# 01_MCU.net
KiCad netlist of a schematic drawn in Altium Designer
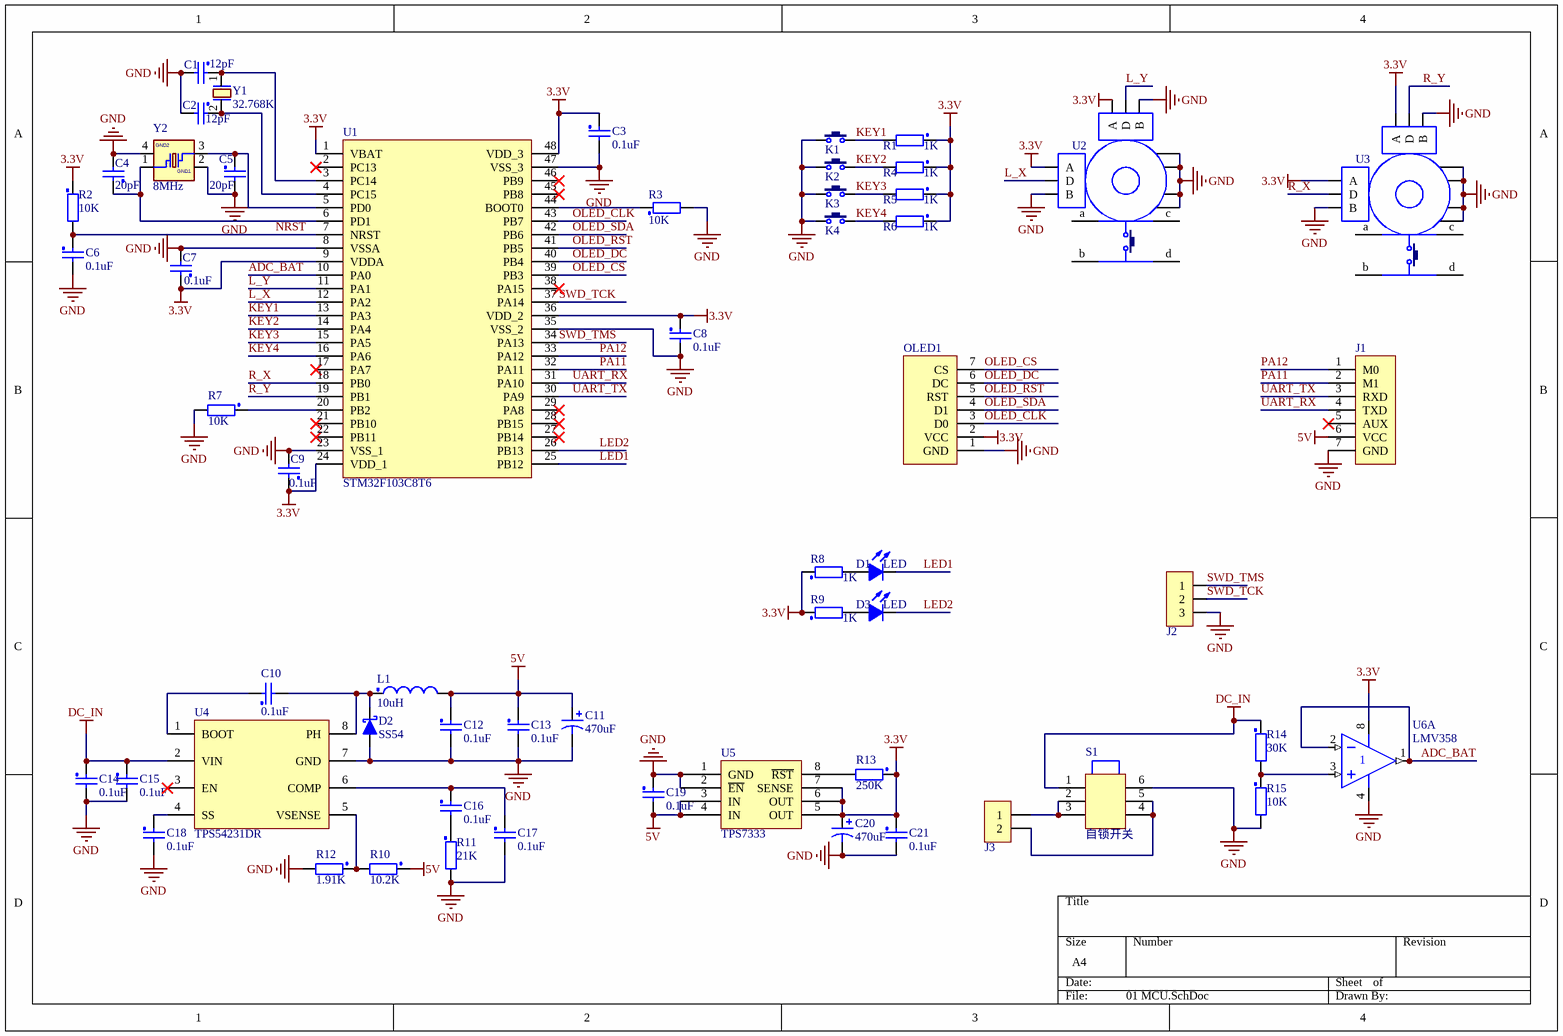
[diagram p0: 01 MCU.SchDoc]

(export (version "E")
  (design (tool "Eeschema 10.0.6"))
  (components
    (comp (ref "C1")
      (value "12pF")
      (footprint "cap0603")
      (description "贴片电容")
      (fields (field (name "PUBLISHER") "Altium Limited"))
      (libsource (lib "元件库") (part "Cap"))
    )
    (comp (ref "C2")
      (value "12pF")
      (footprint "cap0603")
      (description "贴片电容")
      (fields (field (name "PUBLISHER") "Altium Limited"))
      (libsource (lib "元件库") (part "Cap"))
    )
    (comp (ref "C3")
      (value "0.1uF")
      (footprint "cap0603")
      (description "贴片电容")
      (fields (field (name "PUBLISHER") "Altium Limited"))
      (libsource (lib "元件库") (part "Cap"))
    )
    (comp (ref "C4")
      (value "20pF")
      (footprint "cap0603")
      (description "贴片电容")
      (fields (field (name "PUBLISHER") "Altium Limited"))
      (libsource (lib "元件库") (part "Cap"))
    )
    (comp (ref "C5")
      (value "20pF")
      (footprint "cap0603")
      (description "贴片电容")
      (fields (field (name "PUBLISHER") "Altium Limited"))
      (libsource (lib "元件库") (part "Cap"))
    )
    (comp (ref "C6")
      (value "0.1uF")
      (footprint "cap0603")
      (description "贴片电容")
      (fields (field (name "PUBLISHER") "Altium Limited"))
      (libsource (lib "元件库") (part "Cap"))
    )
    (comp (ref "C7")
      (value "0.1uF")
      (footprint "cap0603")
      (description "贴片电容")
      (fields (field (name "PUBLISHER") "Altium Limited"))
      (libsource (lib "元件库") (part "Cap"))
    )
    (comp (ref "C8")
      (value "0.1uF")
      (footprint "cap0603")
      (description "贴片电容")
      (fields (field (name "PUBLISHER") "Altium Limited"))
      (libsource (lib "元件库") (part "Cap"))
    )
    (comp (ref "C9")
      (value "0.1uF")
      (footprint "cap0603")
      (description "贴片电容")
      (fields (field (name "PUBLISHER") "Altium Limited"))
      (libsource (lib "元件库") (part "Cap"))
    )
    (comp (ref "C10")
      (value "0.1uF")
      (footprint "cap0603")
      (description "贴片电容")
      (fields (field (name "PUBLISHER") "Altium Limited"))
      (libsource (lib "元件库") (part "Cap"))
    )
    (comp (ref "C11")
      (value "470uF")
      (footprint "Cap8x10.5mm")
      (description "贴片电解电容 8*10.5mm")
      (fields (field (name "PUBLISHER") "Altium Limited"))
      (libsource (lib "元件库") (part "Cap Pol"))
    )
    (comp (ref "C12")
      (value "0.1uF")
      (footprint "cap0603")
      (description "贴片电容")
      (fields (field (name "PUBLISHER") "Altium Limited"))
      (libsource (lib "元件库") (part "Cap"))
    )
    (comp (ref "C13")
      (value "0.1uF")
      (footprint "cap0603")
      (description "贴片电容")
      (fields (field (name "PUBLISHER") "Altium Limited"))
      (libsource (lib "元件库") (part "Cap"))
    )
    (comp (ref "C14")
      (value "0.1uF")
      (footprint "cap0603")
      (description "贴片电容")
      (fields (field (name "PUBLISHER") "Altium Limited"))
      (libsource (lib "元件库") (part "Cap"))
    )
    (comp (ref "C15")
      (value "0.1uF")
      (footprint "cap0603")
      (description "贴片电容")
      (fields (field (name "PUBLISHER") "Altium Limited"))
      (libsource (lib "元件库") (part "Cap"))
    )
    (comp (ref "C16")
      (value "0.1uF")
      (footprint "cap0603")
      (description "贴片电容")
      (fields (field (name "PUBLISHER") "Altium Limited"))
      (libsource (lib "元件库") (part "Cap"))
    )
    (comp (ref "C17")
      (value "0.1uF")
      (footprint "cap0603")
      (description "贴片电容")
      (fields (field (name "PUBLISHER") "Altium Limited"))
      (libsource (lib "元件库") (part "Cap"))
    )
    (comp (ref "C18")
      (value "0.1uF")
      (footprint "cap0603")
      (description "贴片电容")
      (fields (field (name "PUBLISHER") "Altium Limited"))
      (libsource (lib "元件库") (part "Cap"))
    )
    (comp (ref "C19")
      (value "0.1uF")
      (footprint "cap0603")
      (description "贴片电容")
      (fields (field (name "PUBLISHER") "Altium Limited"))
      (libsource (lib "元件库") (part "Cap"))
    )
    (comp (ref "C20")
      (value "470uF")
      (footprint "Cap8x10.5mm")
      (description "贴片电解电容 8*10.5mm")
      (fields (field (name "PUBLISHER") "Altium Limited"))
      (libsource (lib "元件库") (part "Cap Pol"))
    )
    (comp (ref "C21")
      (value "0.1uF")
      (footprint "cap0603")
      (description "贴片电容")
      (fields (field (name "PUBLISHER") "Altium Limited"))
      (libsource (lib "元件库") (part "Cap"))
    )
    (comp (ref "D1")
      (value "LED")
      (footprint "LED")
      (description "贴片0805")
      (fields (field (name "PUBLISHER") "Altium Limited"))
      (libsource (lib "元件库") (part "LED"))
    )
    (comp (ref "D2")
      (value "SS54")
      (footprint "SMA(DO-214AC)")
      (description "Schottky Diode")
      (fields (field (name "PUBLISHER") "Altium Limited"))
      (libsource (lib "元件库") (part "D Schottky"))
    )
    (comp (ref "D3")
      (value "LED")
      (footprint "LED")
      (description "贴片0805")
      (fields (field (name "PUBLISHER") "Altium Limited"))
      (libsource (lib "元件库") (part "LED"))
    )
    (comp (ref "J1")
      (value "1x7m")
      (footprint "uart_nrf24l01")
      (description "2.54mm母排座")
      (libsource (lib "元件库") (part "无线串口模块"))
    )
    (comp (ref "J2")
      (value "1X3")
      (footprint "HDR-1X3_SWD")
      (description "2.54mm公排针")
      (fields (field (name "版权归属") "源创客"))
      (libsource (lib "元件库") (part "Header 3"))
    )
    (comp (ref "J3")
      (value "1X2")
      (footprint "HDR-1X2")
      (description "不用焊")
      (fields (field (name "版权归属") "源创客"))
      (libsource (lib "元件库") (part "Header 2"))
    )
    (comp (ref "K1")
      (value "KEY")
      (footprint "key")
      (description "按键")
      (fields (field (name "版权归属") "源创客"))
      (libsource (lib "元件库") (part "KEY"))
    )
    (comp (ref "K2")
      (value "KEY")
      (footprint "key")
      (description "按键")
      (fields (field (name "版权归属") "源创客"))
      (libsource (lib "元件库") (part "KEY"))
    )
    (comp (ref "K3")
      (value "KEY")
      (footprint "key")
      (description "按键")
      (fields (field (name "版权归属") "源创客"))
      (libsource (lib "元件库") (part "KEY"))
    )
    (comp (ref "K4")
      (value "KEY")
      (footprint "key")
      (description "按键")
      (fields (field (name "版权归属") "源创客"))
      (libsource (lib "元件库") (part "KEY"))
    )
    (comp (ref "L1")
      (value "10uH")
      (footprint "CD43")
      (description "贴片功率电感")
      (fields (field (name "PUBLISHER") "Altium Limited"))
      (libsource (lib "元件库") (part "Inductor"))
    )
    (comp (ref "OLED1")
      (value "2.541x7母排")
      (footprint "LQ_OLED128X64去丝印")
      (libsource (lib "四轮组原理图元件库") (part "OLED"))
    )
    (comp (ref "R1")
      (value "1K")
      (footprint "res0603")
      (description "贴片电阻")
      (fields (field (name "PUBLISHER") "Altium Limited"))
      (libsource (lib "") (part "Res_1"))
    )
    (comp (ref "R2")
      (value "10K")
      (footprint "res0603")
      (description "贴片电阻")
      (fields (field (name "PUBLISHER") "Altium Limited"))
      (libsource (lib "元件库") (part "Res"))
    )
    (comp (ref "R3")
      (value "10K")
      (footprint "res0603")
      (description "贴片电阻")
      (fields (field (name "PUBLISHER") "Altium Limited"))
      (libsource (lib "") (part "Res_2"))
    )
    (comp (ref "R4")
      (value "1K")
      (footprint "res0603")
      (description "贴片电阻")
      (fields (field (name "PUBLISHER") "Altium Limited"))
      (libsource (lib "") (part "Res_1"))
    )
    (comp (ref "R5")
      (value "1K")
      (footprint "res0603")
      (description "贴片电阻")
      (fields (field (name "PUBLISHER") "Altium Limited"))
      (libsource (lib "") (part "Res_1"))
    )
    (comp (ref "R6")
      (value "1K")
      (footprint "res0603")
      (description "贴片电阻")
      (fields (field (name "PUBLISHER") "Altium Limited"))
      (libsource (lib "") (part "Res_1"))
    )
    (comp (ref "R7")
      (value "10K")
      (footprint "res0603")
      (description "贴片电阻")
      (fields (field (name "PUBLISHER") "Altium Limited"))
      (libsource (lib "") (part "Res_1"))
    )
    (comp (ref "R8")
      (value "1K")
      (footprint "res0603")
      (description "贴片电阻")
      (fields (field (name "PUBLISHER") "Altium Limited"))
      (libsource (lib "") (part "Res_2"))
    )
    (comp (ref "R9")
      (value "1K")
      (footprint "res0603")
      (description "贴片电阻")
      (fields (field (name "PUBLISHER") "Altium Limited"))
      (libsource (lib "") (part "Res_2"))
    )
    (comp (ref "R10")
      (value "10.2K")
      (footprint "res0603")
      (description "贴片电阻")
      (fields (field (name "PUBLISHER") "Altium Limited"))
      (libsource (lib "") (part "Res_1"))
    )
    (comp (ref "R11")
      (value "21K")
      (footprint "res0603")
      (description "贴片电阻")
      (fields (field (name "PUBLISHER") "Altium Limited"))
      (libsource (lib "元件库") (part "Res"))
    )
    (comp (ref "R12")
      (value "1.91K")
      (footprint "res0603")
      (description "贴片电阻")
      (fields (field (name "PUBLISHER") "Altium Limited"))
      (libsource (lib "") (part "Res_1"))
    )
    (comp (ref "R13")
      (value "250K")
      (footprint "res0603")
      (description "贴片电阻")
      (fields (field (name "PUBLISHER") "Altium Limited"))
      (libsource (lib "") (part "Res_1"))
    )
    (comp (ref "R14")
      (value "30K")
      (footprint "res0603")
      (description "贴片电阻")
      (fields (field (name "PUBLISHER") "Altium Limited"))
      (libsource (lib "元件库") (part "Res"))
    )
    (comp (ref "R15")
      (value "10K")
      (footprint "res0603")
      (description "贴片电阻")
      (fields (field (name "PUBLISHER") "Altium Limited"))
      (libsource (lib "元件库") (part "Res"))
    )
    (comp (ref "S1")
      (value "自锁开关")
      (footprint "6pswitch7*7mm")
      (description "按键六脚开关,自锁7*7mm")
      (libsource (lib "元件库") (part "自锁开关"))
    )
    (comp (ref "U1")
      (value "STM32F103C8T6")
      (footprint "LQFP-48_7x7x05P")
      (libsource (lib "元件库") (part "STM32F103C8T6"))
    )
    (comp (ref "U2")
      (value "手柄摇杆电位器")
      (footprint "摇杆")
      (description "型号RKJXV1224005")
      (libsource (lib "元件库") (part "手柄摇杆电位器"))
    )
    (comp (ref "U3")
      (value "手柄摇杆电位器")
      (footprint "摇杆")
      (description "型号RKJXV1224005")
      (libsource (lib "元件库") (part "手柄摇杆电位器"))
    )
    (comp (ref "U4")
      (value "TPS54231DR")
      (footprint "SOIC-8_150mil")
      (description "DC-DC芯片,3.5V~28V输入,2A输出")
      (libsource (lib "元件库") (part "TPS54231DR"))
    )
    (comp (ref "U5")
      (value "TPS7333")
      (footprint "SOP8")
      (description "TPS73系列电源IC")
      (libsource (lib "元件库") (part "TPS7333"))
    )
    (comp (ref "U6")
      (value "LMV358")
      (footprint "OPA2350")
      (description "运放")
      (fields (field (name "PUBLISHER") "Altium Limited"))
      (libsource (lib "元件库") (part "LMV358"))
    )
    (comp (ref "Y1")
      (value "32.768K")
      (footprint "SMD3215")
      (description "晶振 32.768KHZ 12.5PF")
      (libsource (lib "元件库") (part "CRYSTAL"))
    )
    (comp (ref "Y2")
      (value "8MHz")
      (footprint "SMD3225")
      (description "无源晶振 8MHZ 20pF 3.2X2.5MM SMD")
      (libsource (lib "元件库") (part "CRYSTAL_JXS63"))
    )
  )
  (nets
    (net (code "1") (name "/ADC_BAT") (class "Default")
      (node (ref "U1") (pin "10") (pinfunction "PA0_10") (pintype "passive"))
      (node (ref "U6") (pin "1") (pinfunction "OUT_1") (pintype "output"))
      (node (ref "U6") (pin "2") (pinfunction "IN-_2") (pintype "input"))
    )
    (net (code "2") (name "/KEY1") (class "Default")
      (node (ref "K1") (pin "2") (pinfunction "2_2") (pintype "passive"))
      (node (ref "R1") (pin "2") (pinfunction "2_2") (pintype "passive"))
      (node (ref "U1") (pin "13") (pinfunction "PA3_13") (pintype "passive"))
    )
    (net (code "3") (name "/KEY2") (class "Default")
      (node (ref "K2") (pin "2") (pinfunction "2_2") (pintype "passive"))
      (node (ref "R4") (pin "2") (pinfunction "2_2") (pintype "passive"))
      (node (ref "U1") (pin "14") (pinfunction "PA4_14") (pintype "passive"))
    )
    (net (code "4") (name "/KEY3") (class "Default")
      (node (ref "K3") (pin "2") (pinfunction "2_2") (pintype "passive"))
      (node (ref "R5") (pin "2") (pinfunction "2_2") (pintype "passive"))
      (node (ref "U1") (pin "15") (pinfunction "PA5_15") (pintype "passive"))
    )
    (net (code "5") (name "/KEY4") (class "Default")
      (node (ref "K4") (pin "2") (pinfunction "2_2") (pintype "passive"))
      (node (ref "R6") (pin "2") (pinfunction "2_2") (pintype "passive"))
      (node (ref "U1") (pin "16") (pinfunction "PA6_16") (pintype "passive"))
    )
    (net (code "6") (name "/LED1") (class "Default")
      (node (ref "D1") (pin "2") (pinfunction "K_2") (pintype "passive"))
      (node (ref "U1") (pin "25") (pinfunction "PB12_25") (pintype "passive"))
    )
    (net (code "7") (name "/LED2") (class "Default")
      (node (ref "D3") (pin "2") (pinfunction "K_2") (pintype "passive"))
      (node (ref "U1") (pin "26") (pinfunction "PB13_26") (pintype "passive"))
    )
    (net (code "8") (name "/L_X") (class "Default")
      (node (ref "U1") (pin "12") (pinfunction "PA2_12") (pintype "passive"))
      (node (ref "U2") (pin "2") (pinfunction "D_2") (pintype "passive"))
    )
    (net (code "9") (name "/L_Y") (class "Default")
      (node (ref "U1") (pin "11") (pinfunction "PA1_11") (pintype "passive"))
      (node (ref "U2") (pin "5") (pinfunction "D_5") (pintype "passive"))
    )
    (net (code "10") (name "/NRST") (class "Default")
      (node (ref "C6") (pin "1") (pinfunction "1_1") (pintype "passive"))
      (node (ref "R2") (pin "2") (pinfunction "2_2") (pintype "passive"))
      (node (ref "U1") (pin "7") (pinfunction "NRST_7") (pintype "passive"))
    )
    (net (code "11") (name "/OLED_CLK") (class "Default")
      (node (ref "OLED1") (pin "3") (pinfunction "D0_3") (pintype "passive"))
      (node (ref "U1") (pin "43") (pinfunction "PB7_43") (pintype "passive"))
    )
    (net (code "12") (name "/OLED_CS") (class "Default")
      (node (ref "OLED1") (pin "7") (pinfunction "CS_7") (pintype "passive"))
      (node (ref "U1") (pin "39") (pinfunction "PB3_39") (pintype "passive"))
    )
    (net (code "13") (name "/OLED_DC") (class "Default")
      (node (ref "OLED1") (pin "6") (pinfunction "DC_6") (pintype "passive"))
      (node (ref "U1") (pin "40") (pinfunction "PB4_40") (pintype "passive"))
    )
    (net (code "14") (name "/OLED_RST") (class "Default")
      (node (ref "OLED1") (pin "5") (pinfunction "RST_5") (pintype "passive"))
      (node (ref "U1") (pin "41") (pinfunction "PB5_41") (pintype "passive"))
    )
    (net (code "15") (name "/OLED_SDA") (class "Default")
      (node (ref "OLED1") (pin "4") (pinfunction "D1_4") (pintype "passive"))
      (node (ref "U1") (pin "42") (pinfunction "PB6_42") (pintype "passive"))
    )
    (net (code "16") (name "/PA11") (class "Default")
      (node (ref "J1") (pin "2") (pinfunction "M1_2") (pintype "passive"))
      (node (ref "U1") (pin "32") (pinfunction "PA11_32") (pintype "passive"))
    )
    (net (code "17") (name "/PA12") (class "Default")
      (node (ref "J1") (pin "1") (pinfunction "M0_1") (pintype "passive"))
      (node (ref "U1") (pin "33") (pinfunction "PA12_33") (pintype "passive"))
    )
    (net (code "18") (name "/R_X") (class "Default")
      (node (ref "U1") (pin "18") (pinfunction "PB0_18") (pintype "passive"))
      (node (ref "U3") (pin "2") (pinfunction "D_2") (pintype "passive"))
    )
    (net (code "19") (name "/R_Y") (class "Default")
      (node (ref "U1") (pin "19") (pinfunction "PB1_19") (pintype "passive"))
      (node (ref "U3") (pin "5") (pinfunction "D_5") (pintype "passive"))
    )
    (net (code "20") (name "/SWD_TCK") (class "Default")
      (node (ref "J2") (pin "2") (pinfunction "2_2") (pintype "passive"))
      (node (ref "U1") (pin "37") (pinfunction "PA14_37") (pintype "passive"))
    )
    (net (code "21") (name "/SWD_TMS") (class "Default")
      (node (ref "J2") (pin "1") (pinfunction "1_1") (pintype "passive"))
      (node (ref "U1") (pin "34") (pinfunction "PA13_34") (pintype "passive"))
    )
    (net (code "22") (name "/UART_RX") (class "Default")
      (node (ref "J1") (pin "4") (pinfunction "TXD_4") (pintype "passive"))
      (node (ref "U1") (pin "31") (pinfunction "PA10_31") (pintype "passive"))
    )
    (net (code "23") (name "/UART_TX") (class "Default")
      (node (ref "J1") (pin "3") (pinfunction "RXD_3") (pintype "passive"))
      (node (ref "U1") (pin "30") (pinfunction "PA9_30") (pintype "passive"))
    )
    (net (code "24") (name "3.3V") (class "Default")
      (node (ref "C20") (pin "1") (pinfunction "1_1") (pintype "passive"))
      (node (ref "C21") (pin "1") (pinfunction "1_1") (pintype "passive"))
      (node (ref "C3") (pin "1") (pinfunction "1_1") (pintype "passive"))
      (node (ref "C7") (pin "1") (pinfunction "1_1") (pintype "passive"))
      (node (ref "C8") (pin "1") (pinfunction "1_1") (pintype "passive"))
      (node (ref "C9") (pin "1") (pinfunction "1_1") (pintype "passive"))
      (node (ref "OLED1") (pin "2") (pinfunction "VCC_2") (pintype "passive"))
      (node (ref "R1") (pin "1") (pinfunction "1_1") (pintype "passive"))
      (node (ref "R13") (pin "1") (pinfunction "1_1") (pintype "passive"))
      (node (ref "R2") (pin "1") (pinfunction "1_1") (pintype "passive"))
      (node (ref "R4") (pin "1") (pinfunction "1_1") (pintype "passive"))
      (node (ref "R5") (pin "1") (pinfunction "1_1") (pintype "passive"))
      (node (ref "R6") (pin "1") (pinfunction "1_1") (pintype "passive"))
      (node (ref "R8") (pin "1") (pinfunction "1_1") (pintype "passive"))
      (node (ref "R9") (pin "1") (pinfunction "1_1") (pintype "passive"))
      (node (ref "U1") (pin "1") (pinfunction "VBAT_1") (pintype "passive"))
      (node (ref "U1") (pin "24") (pinfunction "VDD_1_24") (pintype "passive"))
      (node (ref "U1") (pin "36") (pinfunction "VDD_2_36") (pintype "passive"))
      (node (ref "U1") (pin "48") (pinfunction "VDD_3_48") (pintype "passive"))
      (node (ref "U1") (pin "9") (pinfunction "VDDA_9") (pintype "passive"))
      (node (ref "U2") (pin "3") (pinfunction "A_3") (pintype "passive"))
      (node (ref "U2") (pin "4") (pinfunction "A_4") (pintype "passive"))
      (node (ref "U3") (pin "3") (pinfunction "A_3") (pintype "passive"))
      (node (ref "U3") (pin "4") (pinfunction "A_4") (pintype "passive"))
      (node (ref "U5") (pin "5") (pinfunction "OUT_5") (pintype "passive"))
      (node (ref "U5") (pin "6") (pinfunction "OUT_6") (pintype "passive"))
      (node (ref "U5") (pin "7") (pinfunction "SENSE_7") (pintype "passive"))
      (node (ref "U6") (pin "8") (pinfunction "V+_8") (pintype "power_in"))
    )
    (net (code "25") (name "5V") (class "Default")
      (node (ref "C11") (pin "1") (pinfunction "1_1") (pintype "passive"))
      (node (ref "C12") (pin "1") (pinfunction "1_1") (pintype "passive"))
      (node (ref "C13") (pin "1") (pinfunction "1_1") (pintype "passive"))
      (node (ref "C19") (pin "2") (pinfunction "2_2") (pintype "passive"))
      (node (ref "J1") (pin "6") (pinfunction "VCC_6") (pintype "passive"))
      (node (ref "L1") (pin "2") (pinfunction "2_2") (pintype "passive"))
      (node (ref "R10") (pin "1") (pinfunction "1_1") (pintype "passive"))
      (node (ref "U5") (pin "3") (pinfunction "IN_3") (pintype "passive"))
      (node (ref "U5") (pin "4") (pinfunction "IN_4") (pintype "passive"))
    )
    (net (code "26") (name "DC_IN") (class "Default")
      (node (ref "C14") (pin "1") (pinfunction "1_1") (pintype "passive"))
      (node (ref "C15") (pin "1") (pinfunction "1_1") (pintype "passive"))
      (node (ref "R14") (pin "1") (pinfunction "1_1") (pintype "passive"))
      (node (ref "S1") (pin "1") (pintype "passive"))
      (node (ref "U4") (pin "2") (pinfunction "VIN_2") (pintype "passive"))
    )
    (net (code "27") (name "GND") (class "Default")
      (node (ref "C1") (pin "2") (pinfunction "2_2") (pintype "passive"))
      (node (ref "C11") (pin "2") (pinfunction "2_2") (pintype "passive"))
      (node (ref "C12") (pin "2") (pinfunction "2_2") (pintype "passive"))
      (node (ref "C13") (pin "2") (pinfunction "2_2") (pintype "passive"))
      (node (ref "C14") (pin "2") (pinfunction "2_2") (pintype "passive"))
      (node (ref "C15") (pin "2") (pinfunction "2_2") (pintype "passive"))
      (node (ref "C17") (pin "2") (pinfunction "2_2") (pintype "passive"))
      (node (ref "C18") (pin "2") (pinfunction "2_2") (pintype "passive"))
      (node (ref "C19") (pin "1") (pinfunction "1_1") (pintype "passive"))
      (node (ref "C2") (pin "2") (pinfunction "2_2") (pintype "passive"))
      (node (ref "C20") (pin "2") (pinfunction "2_2") (pintype "passive"))
      (node (ref "C21") (pin "2") (pinfunction "2_2") (pintype "passive"))
      (node (ref "C3") (pin "2") (pinfunction "2_2") (pintype "passive"))
      (node (ref "C4") (pin "2") (pinfunction "2_2") (pintype "passive"))
      (node (ref "C5") (pin "2") (pinfunction "2_2") (pintype "passive"))
      (node (ref "C6") (pin "2") (pinfunction "2_2") (pintype "passive"))
      (node (ref "C7") (pin "2") (pinfunction "2_2") (pintype "passive"))
      (node (ref "C8") (pin "2") (pinfunction "2_2") (pintype "passive"))
      (node (ref "C9") (pin "2") (pinfunction "2_2") (pintype "passive"))
      (node (ref "D2") (pin "1") (pinfunction "A_1") (pintype "passive"))
      (node (ref "J1") (pin "7") (pinfunction "GND_7") (pintype "passive"))
      (node (ref "J2") (pin "3") (pinfunction "3_3") (pintype "passive"))
      (node (ref "K1") (pin "1") (pinfunction "1_1") (pintype "passive"))
      (node (ref "K2") (pin "1") (pinfunction "1_1") (pintype "passive"))
      (node (ref "K3") (pin "1") (pinfunction "1_1") (pintype "passive"))
      (node (ref "K4") (pin "1") (pinfunction "1_1") (pintype "passive"))
      (node (ref "OLED1") (pin "1") (pinfunction "GND_1") (pintype "passive"))
      (node (ref "R11") (pin "2") (pinfunction "2_2") (pintype "passive"))
      (node (ref "R12") (pin "2") (pinfunction "2_2") (pintype "passive"))
      (node (ref "R15") (pin "2") (pinfunction "2_2") (pintype "passive"))
      (node (ref "R3") (pin "2") (pinfunction "2_2") (pintype "passive"))
      (node (ref "R7") (pin "2") (pinfunction "2_2") (pintype "passive"))
      (node (ref "S1") (pin "6") (pinfunction "6_6") (pintype "passive"))
      (node (ref "U1") (pin "23") (pinfunction "VSS_1_23") (pintype "passive"))
      (node (ref "U1") (pin "35") (pinfunction "VSS_2_35") (pintype "passive"))
      (node (ref "U1") (pin "47") (pinfunction "VSS_3_47") (pintype "passive"))
      (node (ref "U1") (pin "8") (pinfunction "VSSA_8") (pintype "passive"))
      (node (ref "U2") (pin "1") (pinfunction "B_1") (pintype "passive"))
      (node (ref "U2") (pin "10") (pinfunction "10_10") (pintype "passive"))
      (node (ref "U2") (pin "6") (pinfunction "B_6") (pintype "passive"))
      (node (ref "U2") (pin "7") (pinfunction "7_7") (pintype "passive"))
      (node (ref "U2") (pin "8") (pinfunction "8_8") (pintype "passive"))
      (node (ref "U2") (pin "9") (pinfunction "9_9") (pintype "passive"))
      (node (ref "U3") (pin "1") (pinfunction "B_1") (pintype "passive"))
      (node (ref "U3") (pin "10") (pinfunction "10_10") (pintype "passive"))
      (node (ref "U3") (pin "6") (pinfunction "B_6") (pintype "passive"))
      (node (ref "U3") (pin "7") (pinfunction "7_7") (pintype "passive"))
      (node (ref "U3") (pin "8") (pinfunction "8_8") (pintype "passive"))
      (node (ref "U3") (pin "9") (pinfunction "9_9") (pintype "passive"))
      (node (ref "U4") (pin "7") (pinfunction "GND_7") (pintype "passive"))
      (node (ref "U5") (pin "1") (pinfunction "GND_1") (pintype "passive"))
      (node (ref "U5") (pin "2") (pinfunction "~{EN}_2") (pintype "passive"))
      (node (ref "U6") (pin "4") (pinfunction "V-_4") (pintype "power_in"))
      (node (ref "Y2") (pin "2") (pinfunction "GND1_2") (pintype "power_in"))
      (node (ref "Y2") (pin "4") (pinfunction "GND2_4") (pintype "power_in"))
    )
    (net (code "28") (name "Net-(C16-Pad2)") (class "Default")
      (node (ref "C16") (pin "2") (pinfunction "2_2") (pintype "passive"))
      (node (ref "R11") (pin "1") (pinfunction "1_1") (pintype "passive"))
    )
    (net (code "29") (name "Net-(D1-A)") (class "Default")
      (node (ref "D1") (pin "1") (pinfunction "A_1") (pintype "passive"))
      (node (ref "R8") (pin "2") (pinfunction "2_2") (pintype "passive"))
    )
    (net (code "30") (name "Net-(D2-K)") (class "Default")
      (node (ref "C10") (pin "2") (pinfunction "2_2") (pintype "passive"))
      (node (ref "D2") (pin "2") (pinfunction "K_2") (pintype "passive"))
      (node (ref "L1") (pin "1") (pinfunction "1_1") (pintype "passive"))
      (node (ref "U4") (pin "8") (pinfunction "PH_8") (pintype "passive"))
    )
    (net (code "31") (name "Net-(D3-A)") (class "Default")
      (node (ref "D3") (pin "1") (pinfunction "A_1") (pintype "passive"))
      (node (ref "R9") (pin "2") (pinfunction "2_2") (pintype "passive"))
    )
    (net (code "32") (name "Net-(J3-Pad1)") (class "Default")
      (node (ref "J3") (pin "1") (pinfunction "1_1") (pintype "passive"))
      (node (ref "S1") (pin "2") (pintype "passive"))
      (node (ref "S1") (pin "3") (pintype "passive"))
    )
    (net (code "33") (name "Net-(J3-Pad2)") (class "Default")
      (node (ref "J3") (pin "2") (pinfunction "2_2") (pintype "passive"))
      (node (ref "S1") (pin "4") (pinfunction "4_4") (pintype "passive"))
      (node (ref "S1") (pin "5") (pinfunction "5_5") (pintype "passive"))
    )
    (net (code "34") (name "Net-(U1-BOOT0)") (class "Default")
      (node (ref "R3") (pin "1") (pinfunction "1_1") (pintype "passive"))
      (node (ref "U1") (pin "44") (pinfunction "BOOT0_44") (pintype "passive"))
    )
    (net (code "35") (name "Net-(U1-PB2)") (class "Default")
      (node (ref "R7") (pin "1") (pinfunction "1_1") (pintype "passive"))
      (node (ref "U1") (pin "20") (pinfunction "PB2_20") (pintype "passive"))
    )
    (net (code "36") (name "Net-(U1-PC14)") (class "Default")
      (node (ref "C1") (pin "1") (pinfunction "1_1") (pintype "passive"))
      (node (ref "U1") (pin "3") (pinfunction "PC14_3") (pintype "passive"))
      (node (ref "Y1") (pin "1") (pinfunction "1_1") (pintype "passive"))
    )
    (net (code "37") (name "Net-(U1-PC15)") (class "Default")
      (node (ref "C2") (pin "1") (pinfunction "1_1") (pintype "passive"))
      (node (ref "U1") (pin "4") (pinfunction "PC15_4") (pintype "passive"))
      (node (ref "Y1") (pin "2") (pinfunction "2_2") (pintype "passive"))
    )
    (net (code "38") (name "Net-(U1-PD0)") (class "Default")
      (node (ref "C5") (pin "1") (pinfunction "1_1") (pintype "passive"))
      (node (ref "U1") (pin "5") (pinfunction "PD0_5") (pintype "passive"))
      (node (ref "Y2") (pin "3") (pinfunction "3_3") (pintype "passive"))
    )
    (net (code "39") (name "Net-(U1-PD1)") (class "Default")
      (node (ref "C4") (pin "1") (pinfunction "1_1") (pintype "passive"))
      (node (ref "U1") (pin "6") (pinfunction "PD1_6") (pintype "passive"))
      (node (ref "Y2") (pin "1") (pinfunction "1_1") (pintype "passive"))
    )
    (net (code "40") (name "Net-(U4-BOOT)") (class "Default")
      (node (ref "C10") (pin "1") (pinfunction "1_1") (pintype "passive"))
      (node (ref "U4") (pin "1") (pinfunction "BOOT_1") (pintype "passive"))
    )
    (net (code "41") (name "Net-(U4-COMP)") (class "Default")
      (node (ref "C16") (pin "1") (pinfunction "1_1") (pintype "passive"))
      (node (ref "C17") (pin "1") (pinfunction "1_1") (pintype "passive"))
      (node (ref "U4") (pin "6") (pinfunction "COMP_6") (pintype "passive"))
    )
    (net (code "42") (name "Net-(U4-SS)") (class "Default")
      (node (ref "C18") (pin "1") (pinfunction "1_1") (pintype "passive"))
      (node (ref "U4") (pin "4") (pinfunction "SS_4") (pintype "passive"))
    )
    (net (code "43") (name "Net-(U4-VSENSE)") (class "Default")
      (node (ref "R10") (pin "2") (pinfunction "2_2") (pintype "passive"))
      (node (ref "R12") (pin "1") (pinfunction "1_1") (pintype "passive"))
      (node (ref "U4") (pin "5") (pinfunction "VSENSE_5") (pintype "passive"))
    )
    (net (code "44") (name "Net-(U5-~{RST})") (class "Default")
      (node (ref "R13") (pin "2") (pinfunction "2_2") (pintype "passive"))
      (node (ref "U5") (pin "8") (pinfunction "~{RST}_8") (pintype "passive"))
    )
    (net (code "45") (name "Net-(U6A-IN+)") (class "Default")
      (node (ref "R14") (pin "2") (pinfunction "2_2") (pintype "passive"))
      (node (ref "R15") (pin "1") (pinfunction "1_1") (pintype "passive"))
      (node (ref "U6") (pin "3") (pinfunction "IN+_3") (pintype "input"))
    )
    (net (code "46") (name "unconnected-(J1-AUX-Pad5)") (class "Default")
      (node (ref "J1") (pin "5") (pinfunction "AUX_5") (pintype "passive+no_connect"))
    )
    (net (code "47") (name "unconnected-(U1-PA7-Pad17)") (class "Default")
      (node (ref "U1") (pin "17") (pinfunction "PA7_17") (pintype "passive+no_connect"))
    )
    (net (code "48") (name "unconnected-(U1-PA8-Pad29)") (class "Default")
      (node (ref "U1") (pin "29") (pinfunction "PA8_29") (pintype "passive+no_connect"))
    )
    (net (code "49") (name "unconnected-(U1-PA15-Pad38)") (class "Default")
      (node (ref "U1") (pin "38") (pinfunction "PA15_38") (pintype "passive+no_connect"))
    )
    (net (code "50") (name "unconnected-(U1-PB8-Pad45)") (class "Default")
      (node (ref "U1") (pin "45") (pinfunction "PB8_45") (pintype "passive+no_connect"))
    )
    (net (code "51") (name "unconnected-(U1-PB9-Pad46)") (class "Default")
      (node (ref "U1") (pin "46") (pinfunction "PB9_46") (pintype "passive+no_connect"))
    )
    (net (code "52") (name "unconnected-(U1-PB10-Pad21)") (class "Default")
      (node (ref "U1") (pin "21") (pinfunction "PB10_21") (pintype "passive+no_connect"))
    )
    (net (code "53") (name "unconnected-(U1-PB11-Pad22)") (class "Default")
      (node (ref "U1") (pin "22") (pinfunction "PB11_22") (pintype "passive+no_connect"))
    )
    (net (code "54") (name "unconnected-(U1-PB14-Pad27)") (class "Default")
      (node (ref "U1") (pin "27") (pinfunction "PB14_27") (pintype "passive+no_connect"))
    )
    (net (code "55") (name "unconnected-(U1-PB15-Pad28)") (class "Default")
      (node (ref "U1") (pin "28") (pinfunction "PB15_28") (pintype "passive+no_connect"))
    )
    (net (code "56") (name "unconnected-(U1-PC13-Pad2)") (class "Default")
      (node (ref "U1") (pin "2") (pinfunction "PC13_2") (pintype "passive+no_connect"))
    )
    (net (code "57") (name "unconnected-(U2-Pada)") (class "Default")
      (node (ref "U2") (pin "a") (pinfunction "a_a") (pintype "passive"))
    )
    (net (code "58") (name "unconnected-(U2-Padb)") (class "Default")
      (node (ref "U2") (pin "b") (pinfunction "b_b") (pintype "passive"))
    )
    (net (code "59") (name "unconnected-(U2-Padc)") (class "Default")
      (node (ref "U2") (pin "c") (pinfunction "c_c") (pintype "passive"))
    )
    (net (code "60") (name "unconnected-(U2-Padd)") (class "Default")
      (node (ref "U2") (pin "d") (pinfunction "d_d") (pintype "passive"))
    )
    (net (code "61") (name "unconnected-(U3-Pada)") (class "Default")
      (node (ref "U3") (pin "a") (pinfunction "a_a") (pintype "passive"))
    )
    (net (code "62") (name "unconnected-(U3-Padb)") (class "Default")
      (node (ref "U3") (pin "b") (pinfunction "b_b") (pintype "passive"))
    )
    (net (code "63") (name "unconnected-(U3-Padc)") (class "Default")
      (node (ref "U3") (pin "c") (pinfunction "c_c") (pintype "passive"))
    )
    (net (code "64") (name "unconnected-(U3-Padd)") (class "Default")
      (node (ref "U3") (pin "d") (pinfunction "d_d") (pintype "passive"))
    )
    (net (code "65") (name "unconnected-(U4-EN-Pad3)") (class "Default")
      (node (ref "U4") (pin "3") (pinfunction "EN_3") (pintype "passive+no_connect"))
    )
  )
)
